# espnative-deadrail-2-7-rendered.net
KiCad netlist of a schematic drawn in EAGLE
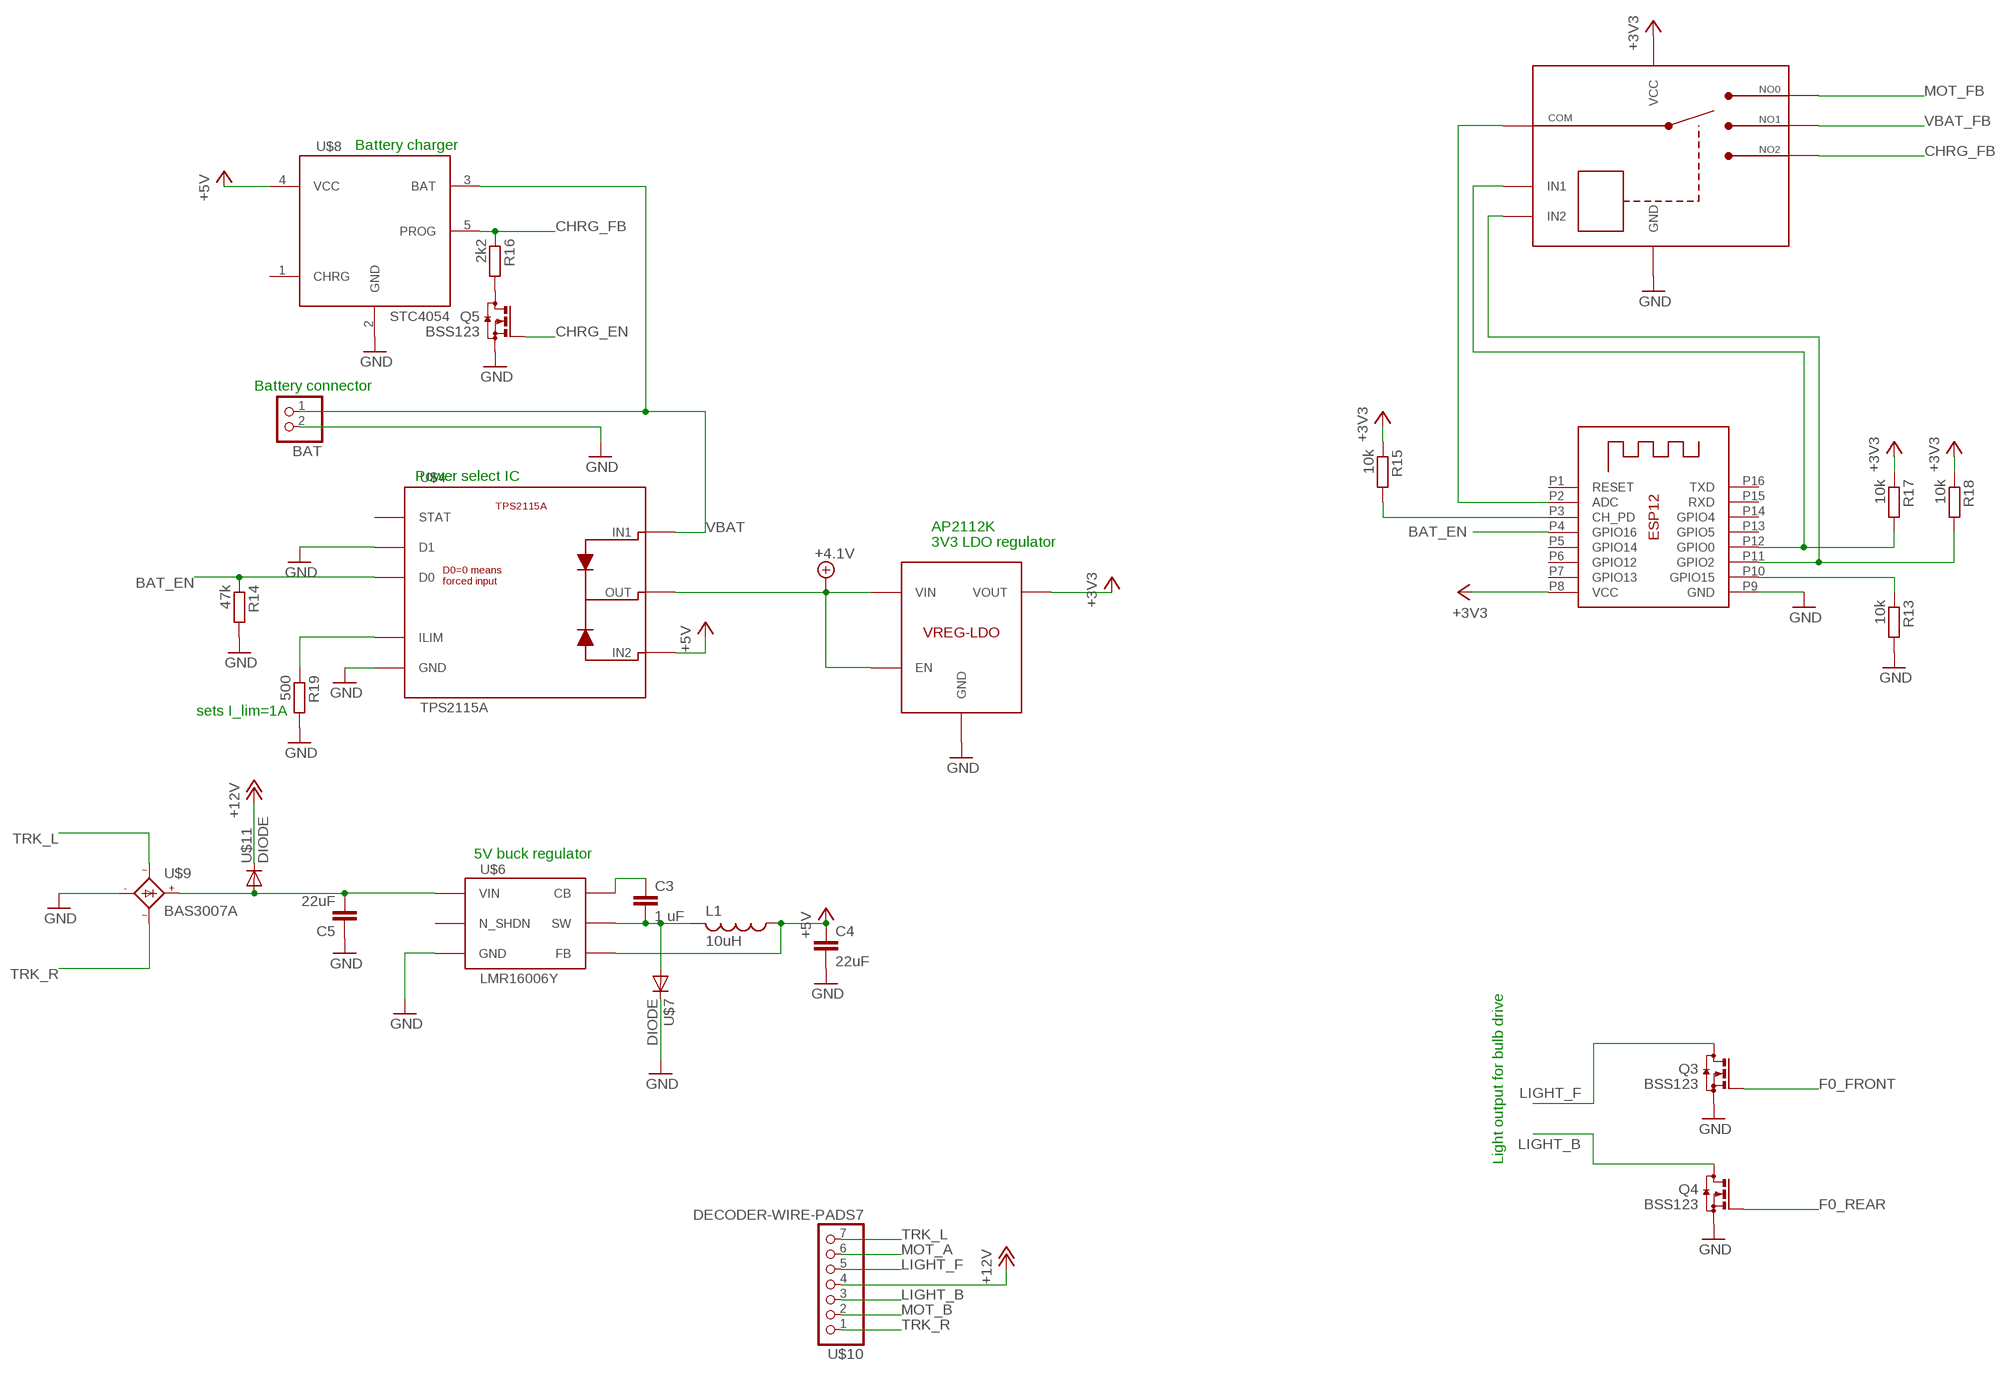
[diagram p0: schematic, sheet 1, part 1 of 2]
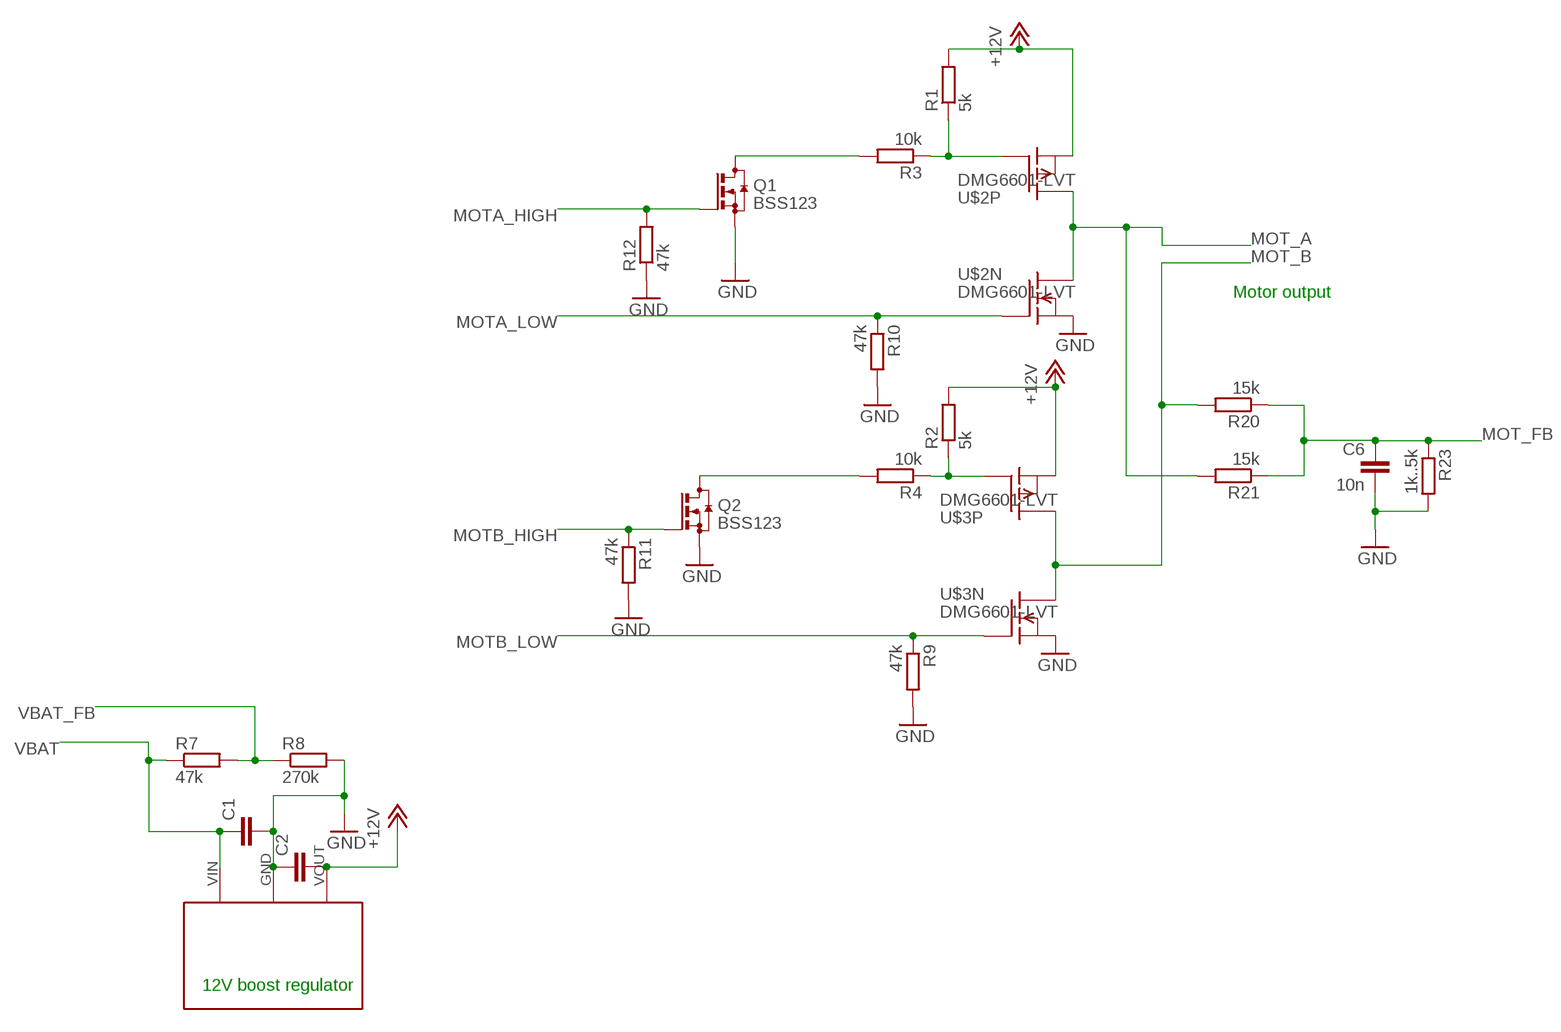
[diagram p1: schematic, sheet 1, part 2 of 2]

(export (version "E")
  (design (tool "Eeschema 10.0.6"))
  (components
    (comp (ref "BAT")
      (value "JST_2PIN-SMT-RA")
      (footprint "eagle-import:JST-PH-2-SMT-RA")
      (libsource (lib "eagle-import") (part "JST_2PIN-SMT-RA"))
    )
    (comp (ref "C1")
      (value "C-EUC1206")
      (footprint "eagle-import:C1206")
      (libsource (lib "eagle-import") (part "C-EUC1206"))
    )
    (comp (ref "C2")
      (value "C-EUC1206")
      (footprint "eagle-import:C1206")
      (libsource (lib "eagle-import") (part "C-EUC1206"))
    )
    (comp (ref "C3")
      (value "1 uF")
      (footprint "eagle-import:C0603")
      (libsource (lib "eagle-import") (part "C-EUC0603"))
    )
    (comp (ref "C4")
      (value "22uF")
      (footprint "eagle-import:C0603")
      (libsource (lib "eagle-import") (part "C-EUC0603"))
    )
    (comp (ref "C5")
      (value "22uF")
      (footprint "eagle-import:C1206")
      (libsource (lib "eagle-import") (part "C-EUC1206"))
    )
    (comp (ref "C6")
      (value "10n")
      (footprint "eagle-import:C0603")
      (libsource (lib "eagle-import") (part "C-EUC0603"))
    )
    (comp (ref "L1")
      (value "10uH")
      (footprint "eagle-import:FDSD0420")
      (libsource (lib "eagle-import") (part "FDSD0420"))
    )
    (comp (ref "Q1")
      (value "BSS123")
      (footprint "eagle-import:SOT23")
      (libsource (lib "eagle-import") (part "BSS123"))
    )
    (comp (ref "Q2")
      (value "BSS123")
      (footprint "eagle-import:SOT23")
      (libsource (lib "eagle-import") (part "BSS123"))
    )
    (comp (ref "Q3")
      (value "BSS123")
      (footprint "eagle-import:SOT23")
      (libsource (lib "eagle-import") (part "BSS123"))
    )
    (comp (ref "Q4")
      (value "BSS123")
      (footprint "eagle-import:SOT23")
      (libsource (lib "eagle-import") (part "BSS123"))
    )
    (comp (ref "Q5")
      (value "BSS123")
      (footprint "eagle-import:SOT23")
      (libsource (lib "eagle-import") (part "BSS123"))
    )
    (comp (ref "R1")
      (value "5k")
      (footprint "eagle-import:R0603")
      (libsource (lib "eagle-import") (part "R-EU_R0603"))
    )
    (comp (ref "R2")
      (value "5k")
      (footprint "eagle-import:R0603")
      (libsource (lib "eagle-import") (part "R-EU_R0603"))
    )
    (comp (ref "R3")
      (value "10k")
      (footprint "eagle-import:R0603")
      (libsource (lib "eagle-import") (part "R-EU_R0603"))
    )
    (comp (ref "R4")
      (value "10k")
      (footprint "eagle-import:R0603")
      (libsource (lib "eagle-import") (part "R-EU_R0603"))
    )
    (comp (ref "R7")
      (value "47k")
      (footprint "eagle-import:R0603")
      (libsource (lib "eagle-import") (part "R-EU_R0603"))
    )
    (comp (ref "R8")
      (value "270k")
      (footprint "eagle-import:R0603")
      (libsource (lib "eagle-import") (part "R-EU_R0603"))
    )
    (comp (ref "R9")
      (value "47k")
      (footprint "eagle-import:R0603")
      (libsource (lib "eagle-import") (part "R-EU_R0603"))
    )
    (comp (ref "R10")
      (value "47k")
      (footprint "eagle-import:R0603")
      (libsource (lib "eagle-import") (part "R-EU_R0603"))
    )
    (comp (ref "R11")
      (value "47k")
      (footprint "eagle-import:R0603")
      (libsource (lib "eagle-import") (part "R-EU_R0603"))
    )
    (comp (ref "R12")
      (value "47k")
      (footprint "eagle-import:R0603")
      (libsource (lib "eagle-import") (part "R-EU_R0603"))
    )
    (comp (ref "R13")
      (value "10k")
      (footprint "eagle-import:R0603")
      (libsource (lib "eagle-import") (part "R-EU_R0603"))
    )
    (comp (ref "R14")
      (value "47k")
      (footprint "eagle-import:R0603")
      (libsource (lib "eagle-import") (part "R-EU_R0603"))
    )
    (comp (ref "R15")
      (value "10k")
      (footprint "eagle-import:R0603")
      (libsource (lib "eagle-import") (part "R-EU_R0603"))
    )
    (comp (ref "R16")
      (value "2k2")
      (footprint "eagle-import:R0603")
      (libsource (lib "eagle-import") (part "R-EU_R0603"))
    )
    (comp (ref "R17")
      (value "10k")
      (footprint "eagle-import:R0603")
      (libsource (lib "eagle-import") (part "R-EU_R0603"))
    )
    (comp (ref "R18")
      (value "10k")
      (footprint "eagle-import:R0603")
      (libsource (lib "eagle-import") (part "R-EU_R0603"))
    )
    (comp (ref "R19")
      (value "500")
      (footprint "eagle-import:R0603")
      (libsource (lib "eagle-import") (part "R-EU_R0603"))
    )
    (comp (ref "R20")
      (value "15k")
      (footprint "eagle-import:R0603")
      (libsource (lib "eagle-import") (part "R-EU_R0603"))
    )
    (comp (ref "R21")
      (value "15k")
      (footprint "eagle-import:R0603")
      (libsource (lib "eagle-import") (part "R-EU_R0603"))
    )
    (comp (ref "R23")
      (value "1k..5k")
      (footprint "eagle-import:R0603")
      (libsource (lib "eagle-import") (part "R-EU_R0603"))
    )
    (comp (ref "U$1")
      (value "AP2112K-3V3")
      (footprint "eagle-import:SOT23-5L")
      (libsource (lib "eagle-import") (part "AP2112K"))
    )
    (comp (ref "U$2")
      (value "DMG6601-LVT")
      (footprint "eagle-import:TSOT-26")
      (libsource (lib "eagle-import") (part "DMG6601-LVT"))
    )
    (comp (ref "U$3")
      (value "DMG6601-LVT")
      (footprint "eagle-import:TSOT-26")
      (libsource (lib "eagle-import") (part "DMG6601-LVT"))
    )
    (comp (ref "U$4")
      (value "TPS2115A")
      (footprint "eagle-import:TSSOP-8")
      (libsource (lib "eagle-import") (part "TPS2115A"))
    )
    (comp (ref "U$5")
      (value "POLOLU-VREG12")
      (footprint "eagle-import:POLOLU-REGULATOR")
      (libsource (lib "eagle-import") (part "POLOLU-VREG12"))
    )
    (comp (ref "U$6")
      (value "LMR16006Y")
      (footprint "eagle-import:SOT23-6")
      (libsource (lib "eagle-import") (part "LMR16006Y"))
    )
    (comp (ref "U$7")
      (value "DIODE")
      (footprint "eagle-import:DIODE-1206")
      (libsource (lib "eagle-import") (part "DIODE"))
    )
    (comp (ref "U$8")
      (value "STC4054")
      (footprint "eagle-import:SOT23-5L")
      (libsource (lib "eagle-import") (part "STC4054"))
    )
    (comp (ref "U$9")
      (value "BAS3007A")
      (footprint "eagle-import:SOT143B")
      (libsource (lib "eagle-import") (part "BAS3007A"))
    )
    (comp (ref "U$10")
      (value "DECODER-WIRE-PADS7")
      (footprint "eagle-import:DECODER-WIRE-PADS")
      (libsource (lib "eagle-import") (part "DECODER-WIRE-PADS7"))
    )
    (comp (ref "U$11")
      (value "DIODE")
      (footprint "eagle-import:DIODE-1206")
      (libsource (lib "eagle-import") (part "DIODE"))
    )
    (comp (ref "U$12")
      (value "TS5A3359")
      (footprint "eagle-import:US8")
      (libsource (lib "eagle-import") (part "TS5A3359"))
    )
    (comp (ref "X1")
      (value "ESP-12-TH")
      (footprint "eagle-import:ESP-12-TH")
      (libsource (lib "eagle-import") (part "ESP-12-TH"))
    )
  )
  (nets
    (net (code "1") (name "+3V3") (class "Default")
      (node (ref "R15") (pin "1") (pinfunction "1_1") (pintype "passive"))
      (node (ref "R17") (pin "1") (pinfunction "1_1") (pintype "passive"))
      (node (ref "R18") (pin "1") (pinfunction "1_1") (pintype "passive"))
      (node (ref "U$1") (pin "5") (pinfunction "VOUT_5") (pintype "bidirectional"))
      (node (ref "U$12") (pin "8") (pinfunction "VCC_8") (pintype "bidirectional"))
      (node (ref "X1") (pin "P8") (pinfunction "VCC_P8") (pintype "power_in"))
    )
    (net (code "2") (name "+4.1V") (class "Default")
      (node (ref "U$1") (pin "1") (pinfunction "VIN_1") (pintype "bidirectional"))
      (node (ref "U$1") (pin "3") (pinfunction "EN_3") (pintype "bidirectional"))
      (node (ref "U$4") (pin "7") (pinfunction "OUT_7") (pintype "bidirectional"))
    )
    (net (code "3") (name "+5V") (class "Default")
      (node (ref "C4") (pin "1") (pinfunction "1_1") (pintype "passive"))
      (node (ref "L1") (pin "P$1") (pinfunction "1_P$1") (pintype "passive"))
      (node (ref "U$4") (pin "6") (pinfunction "IN2_6") (pintype "bidirectional"))
      (node (ref "U$6") (pin "3") (pinfunction "FB_3") (pintype "bidirectional"))
      (node (ref "U$8") (pin "4") (pinfunction "VCC_4") (pintype "bidirectional"))
    )
    (net (code "4") (name "+12V") (class "Default")
      (node (ref "C2") (pin "2") (pinfunction "2_2") (pintype "passive"))
      (node (ref "R1") (pin "2") (pinfunction "2_2") (pintype "passive"))
      (node (ref "R2") (pin "2") (pinfunction "2_2") (pintype "passive"))
      (node (ref "U$10") (pin "4") (pinfunction "4_4") (pintype "passive"))
      (node (ref "U$11") (pin "C") (pinfunction "C_C") (pintype "passive"))
      (node (ref "U$2") (pin "2") (pinfunction "S_2") (pintype "passive"))
      (node (ref "U$3") (pin "2") (pinfunction "S_2") (pintype "passive"))
      (node (ref "U$5") (pin "VOUT") (pinfunction "VOUT_VOUT") (pintype "bidirectional"))
    )
    (net (code "5") (name "/BAT_EN") (class "Default")
      (node (ref "R14") (pin "1") (pinfunction "1_1") (pintype "passive"))
      (node (ref "U$4") (pin "2") (pinfunction "D0_2") (pintype "bidirectional"))
      (node (ref "X1") (pin "P4") (pinfunction "GPIO16_P4") (pintype "bidirectional"))
    )
    (net (code "6") (name "/CHRG_EN") (class "Default")
      (node (ref "Q5") (pin "1") (pinfunction "G_1") (pintype "passive"))
    )
    (net (code "7") (name "/CHRG_FB") (class "Default")
      (node (ref "R16") (pin "1") (pinfunction "1_1") (pintype "passive"))
      (node (ref "U$12") (pin "3") (pinfunction "NO2_3") (pintype "bidirectional"))
      (node (ref "U$8") (pin "5") (pinfunction "PROG_5") (pintype "bidirectional"))
    )
    (net (code "8") (name "/F0_FRONT") (class "Default")
      (node (ref "Q3") (pin "1") (pinfunction "G_1") (pintype "passive"))
    )
    (net (code "9") (name "/F0_REAR") (class "Default")
      (node (ref "Q4") (pin "1") (pinfunction "G_1") (pintype "passive"))
    )
    (net (code "10") (name "/LIGHT_B") (class "Default")
      (node (ref "Q4") (pin "3") (pinfunction "D_3") (pintype "passive"))
      (node (ref "U$10") (pin "3") (pinfunction "3_3") (pintype "passive"))
    )
    (net (code "11") (name "/LIGHT_F") (class "Default")
      (node (ref "Q3") (pin "3") (pinfunction "D_3") (pintype "passive"))
      (node (ref "U$10") (pin "5") (pinfunction "5_5") (pintype "passive"))
    )
    (net (code "12") (name "/MOTA_HIGH") (class "Default")
      (node (ref "Q1") (pin "1") (pinfunction "G_1") (pintype "passive"))
      (node (ref "R12") (pin "2") (pinfunction "2_2") (pintype "passive"))
    )
    (net (code "13") (name "/MOTA_LOW") (class "Default")
      (node (ref "R10") (pin "1") (pinfunction "1_1") (pintype "passive"))
      (node (ref "U$2") (pin "1") (pinfunction "G_1") (pintype "passive"))
    )
    (net (code "14") (name "/MOTB_HIGH") (class "Default")
      (node (ref "Q2") (pin "1") (pinfunction "G_1") (pintype "passive"))
      (node (ref "R11") (pin "1") (pinfunction "1_1") (pintype "passive"))
    )
    (net (code "15") (name "/MOTB_LOW") (class "Default")
      (node (ref "R9") (pin "1") (pinfunction "1_1") (pintype "passive"))
      (node (ref "U$3") (pin "1") (pinfunction "G_1") (pintype "passive"))
    )
    (net (code "16") (name "/MOT_A") (class "Default")
      (node (ref "R21") (pin "2") (pinfunction "2_2") (pintype "passive"))
      (node (ref "U$10") (pin "6") (pinfunction "6_6") (pintype "passive"))
      (node (ref "U$2") (pin "4") (pinfunction "D_4") (pintype "passive"))
      (node (ref "U$2") (pin "6") (pinfunction "D_6") (pintype "passive"))
    )
    (net (code "17") (name "/MOT_B") (class "Default")
      (node (ref "R20") (pin "2") (pinfunction "2_2") (pintype "passive"))
      (node (ref "U$10") (pin "2") (pinfunction "2_2") (pintype "passive"))
      (node (ref "U$3") (pin "4") (pinfunction "D_4") (pintype "passive"))
      (node (ref "U$3") (pin "6") (pinfunction "D_6") (pintype "passive"))
    )
    (net (code "18") (name "/MOT_FB") (class "Default")
      (node (ref "C6") (pin "1") (pinfunction "1_1") (pintype "passive"))
      (node (ref "R20") (pin "1") (pinfunction "1_1") (pintype "passive"))
      (node (ref "R21") (pin "1") (pinfunction "1_1") (pintype "passive"))
      (node (ref "R23") (pin "1") (pinfunction "1_1") (pintype "passive"))
      (node (ref "U$12") (pin "1") (pinfunction "NO0_1") (pintype "bidirectional"))
    )
    (net (code "19") (name "/TRK_L") (class "Default")
      (node (ref "U$10") (pin "7") (pinfunction "7_7") (pintype "passive"))
      (node (ref "U$9") (pin "2") (pinfunction "AC1_2") (pintype "passive"))
    )
    (net (code "20") (name "/TRK_R") (class "Default")
      (node (ref "U$10") (pin "1") (pinfunction "1_1") (pintype "passive"))
      (node (ref "U$9") (pin "3") (pinfunction "AC2_3") (pintype "passive"))
    )
    (net (code "21") (name "/VBAT") (class "Default")
      (node (ref "BAT") (pin "1") (pinfunction "2_1") (pintype "passive"))
      (node (ref "C1") (pin "1") (pinfunction "1_1") (pintype "passive"))
      (node (ref "R7") (pin "1") (pinfunction "1_1") (pintype "passive"))
      (node (ref "U$4") (pin "8") (pinfunction "IN1_8") (pintype "bidirectional"))
      (node (ref "U$5") (pin "VIN") (pinfunction "VIN_VIN") (pintype "bidirectional"))
      (node (ref "U$8") (pin "3") (pinfunction "BAT_3") (pintype "bidirectional"))
    )
    (net (code "22") (name "/VBAT_FB") (class "Default")
      (node (ref "R7") (pin "2") (pinfunction "2_2") (pintype "passive"))
      (node (ref "R8") (pin "1") (pinfunction "1_1") (pintype "passive"))
      (node (ref "U$12") (pin "2") (pinfunction "NO1_2") (pintype "bidirectional"))
    )
    (net (code "23") (name "GND") (class "Default")
      (node (ref "BAT") (pin "2") (pinfunction "1_2") (pintype "passive"))
      (node (ref "C1") (pin "2") (pinfunction "2_2") (pintype "passive"))
      (node (ref "C2") (pin "1") (pinfunction "1_1") (pintype "passive"))
      (node (ref "C4") (pin "2") (pinfunction "2_2") (pintype "passive"))
      (node (ref "C5") (pin "1") (pinfunction "1_1") (pintype "passive"))
      (node (ref "C6") (pin "2") (pinfunction "2_2") (pintype "passive"))
      (node (ref "Q1") (pin "2") (pinfunction "S_2") (pintype "passive"))
      (node (ref "Q2") (pin "2") (pinfunction "S_2") (pintype "passive"))
      (node (ref "Q3") (pin "2") (pinfunction "S_2") (pintype "passive"))
      (node (ref "Q4") (pin "2") (pinfunction "S_2") (pintype "passive"))
      (node (ref "Q5") (pin "2") (pinfunction "S_2") (pintype "passive"))
      (node (ref "R10") (pin "2") (pinfunction "2_2") (pintype "passive"))
      (node (ref "R11") (pin "2") (pinfunction "2_2") (pintype "passive"))
      (node (ref "R12") (pin "1") (pinfunction "1_1") (pintype "passive"))
      (node (ref "R13") (pin "2") (pinfunction "2_2") (pintype "passive"))
      (node (ref "R14") (pin "2") (pinfunction "2_2") (pintype "passive"))
      (node (ref "R19") (pin "2") (pinfunction "2_2") (pintype "passive"))
      (node (ref "R23") (pin "2") (pinfunction "2_2") (pintype "passive"))
      (node (ref "R8") (pin "2") (pinfunction "2_2") (pintype "passive"))
      (node (ref "R9") (pin "2") (pinfunction "2_2") (pintype "passive"))
      (node (ref "U$1") (pin "2") (pinfunction "GND_2") (pintype "bidirectional"))
      (node (ref "U$12") (pin "4") (pinfunction "GND_4") (pintype "bidirectional"))
      (node (ref "U$2") (pin "5") (pinfunction "S_5") (pintype "passive"))
      (node (ref "U$3") (pin "5") (pinfunction "S_5") (pintype "passive"))
      (node (ref "U$4") (pin "3") (pinfunction "D1_3") (pintype "bidirectional"))
      (node (ref "U$4") (pin "5") (pinfunction "GND_5") (pintype "bidirectional"))
      (node (ref "U$5") (pin "GND") (pinfunction "GND_GND") (pintype "bidirectional"))
      (node (ref "U$6") (pin "2") (pinfunction "GND_2") (pintype "bidirectional"))
      (node (ref "U$7") (pin "C") (pinfunction "C_C") (pintype "passive"))
      (node (ref "U$8") (pin "2") (pinfunction "GND_2") (pintype "bidirectional"))
      (node (ref "U$9") (pin "1") (pinfunction "-_1") (pintype "passive"))
      (node (ref "X1") (pin "P9") (pinfunction "GND_P9") (pintype "power_in"))
    )
    (net (code "24") (name "Net-(L1-2)") (class "Default")
      (node (ref "C3") (pin "2") (pinfunction "2_2") (pintype "passive"))
      (node (ref "L1") (pin "P$2") (pinfunction "2_P$2") (pintype "passive"))
      (node (ref "U$6") (pin "6") (pinfunction "SW_6") (pintype "bidirectional"))
      (node (ref "U$7") (pin "A") (pinfunction "A_A") (pintype "passive"))
    )
    (net (code "25") (name "Net-(Q1-D)") (class "Default")
      (node (ref "Q1") (pin "3") (pinfunction "D_3") (pintype "passive"))
      (node (ref "R3") (pin "2") (pinfunction "2_2") (pintype "passive"))
    )
    (net (code "26") (name "Net-(Q2-D)") (class "Default")
      (node (ref "Q2") (pin "3") (pinfunction "D_3") (pintype "passive"))
      (node (ref "R4") (pin "2") (pinfunction "2_2") (pintype "passive"))
    )
    (net (code "27") (name "Net-(Q5-D)") (class "Default")
      (node (ref "Q5") (pin "3") (pinfunction "D_3") (pintype "passive"))
      (node (ref "R16") (pin "2") (pinfunction "2_2") (pintype "passive"))
    )
    (net (code "28") (name "Net-(U$2B-G)") (class "Default")
      (node (ref "R1") (pin "1") (pinfunction "1_1") (pintype "passive"))
      (node (ref "R3") (pin "1") (pinfunction "1_1") (pintype "passive"))
      (node (ref "U$2") (pin "3") (pinfunction "G_3") (pintype "passive"))
    )
    (net (code "29") (name "Net-(U$3B-G)") (class "Default")
      (node (ref "R2") (pin "1") (pinfunction "1_1") (pintype "passive"))
      (node (ref "R4") (pin "1") (pinfunction "1_1") (pintype "passive"))
      (node (ref "U$3") (pin "3") (pinfunction "G_3") (pintype "passive"))
    )
    (net (code "30") (name "Net-(U$4-ILIM)") (class "Default")
      (node (ref "R19") (pin "1") (pinfunction "1_1") (pintype "passive"))
      (node (ref "U$4") (pin "4") (pinfunction "ILIM_4") (pintype "bidirectional"))
    )
    (net (code "31") (name "Net-(U$6-CB)") (class "Default")
      (node (ref "C3") (pin "1") (pinfunction "1_1") (pintype "passive"))
      (node (ref "U$6") (pin "1") (pinfunction "CB_1") (pintype "bidirectional"))
    )
    (net (code "32") (name "Net-(U$6-VIN)") (class "Default")
      (node (ref "C5") (pin "2") (pinfunction "2_2") (pintype "passive"))
      (node (ref "U$11") (pin "A") (pinfunction "A_A") (pintype "passive"))
      (node (ref "U$6") (pin "5") (pinfunction "VIN_5") (pintype "bidirectional"))
      (node (ref "U$9") (pin "4") (pinfunction "+_4") (pintype "passive"))
    )
    (net (code "33") (name "Net-(U$12-COM)") (class "Default")
      (node (ref "U$12") (pin "7") (pinfunction "COM_7") (pintype "bidirectional"))
      (node (ref "X1") (pin "P2") (pinfunction "ADC_P2") (pintype "passive"))
    )
    (net (code "34") (name "Net-(U$12-IN1)") (class "Default")
      (node (ref "R17") (pin "2") (pinfunction "2_2") (pintype "passive"))
      (node (ref "U$12") (pin "6") (pinfunction "IN1_6") (pintype "bidirectional"))
      (node (ref "X1") (pin "P12") (pinfunction "GPIO0_P12") (pintype "bidirectional"))
    )
    (net (code "35") (name "Net-(U$12-IN2)") (class "Default")
      (node (ref "R18") (pin "2") (pinfunction "2_2") (pintype "passive"))
      (node (ref "U$12") (pin "5") (pinfunction "IN2_5") (pintype "bidirectional"))
      (node (ref "X1") (pin "P11") (pinfunction "GPIO2_P11") (pintype "bidirectional"))
    )
    (net (code "36") (name "Net-(X1-CH_PD)") (class "Default")
      (node (ref "R15") (pin "2") (pinfunction "2_2") (pintype "passive"))
      (node (ref "X1") (pin "P3") (pinfunction "CH_PD_P3") (pintype "input"))
    )
    (net (code "37") (name "Net-(X1-GPIO15)") (class "Default")
      (node (ref "R13") (pin "1") (pinfunction "1_1") (pintype "passive"))
      (node (ref "X1") (pin "P10") (pinfunction "GPIO15_P10") (pintype "bidirectional"))
    )
    (net (code "38") (name "unconnected-(U$4-STAT-Pad1)") (class "Default")
      (node (ref "U$4") (pin "1") (pinfunction "STAT_1") (pintype "bidirectional"))
    )
    (net (code "39") (name "unconnected-(U$6-N_SHDN-Pad4)") (class "Default")
      (node (ref "U$6") (pin "4") (pinfunction "N_SHDN_4") (pintype "bidirectional"))
    )
    (net (code "40") (name "unconnected-(U$8-CHRG-Pad1)") (class "Default")
      (node (ref "U$8") (pin "1") (pinfunction "CHRG_1") (pintype "bidirectional"))
    )
    (net (code "41") (name "unconnected-(X1-GPIO4-PadP14)") (class "Default")
      (node (ref "X1") (pin "P14") (pinfunction "GPIO4_P14") (pintype "bidirectional"))
    )
    (net (code "42") (name "unconnected-(X1-GPIO5-PadP13)") (class "Default")
      (node (ref "X1") (pin "P13") (pinfunction "GPIO5_P13") (pintype "bidirectional"))
    )
    (net (code "43") (name "unconnected-(X1-GPIO12-PadP6)") (class "Default")
      (node (ref "X1") (pin "P6") (pinfunction "GPIO12_P6") (pintype "bidirectional"))
    )
    (net (code "44") (name "unconnected-(X1-GPIO13-PadP7)") (class "Default")
      (node (ref "X1") (pin "P7") (pinfunction "GPIO13_P7") (pintype "bidirectional"))
    )
    (net (code "45") (name "unconnected-(X1-GPIO14-PadP5)") (class "Default")
      (node (ref "X1") (pin "P5") (pinfunction "GPIO14_P5") (pintype "bidirectional"))
    )
    (net (code "46") (name "unconnected-(X1-RESET-PadP1)") (class "Default")
      (node (ref "X1") (pin "P1") (pinfunction "RESET_P1") (pintype "input"))
    )
    (net (code "47") (name "unconnected-(X1-RXD-PadP15)") (class "Default")
      (node (ref "X1") (pin "P15") (pinfunction "RXD_P15") (pintype "input"))
    )
    (net (code "48") (name "unconnected-(X1-TXD-PadP16)") (class "Default")
      (node (ref "X1") (pin "P16") (pinfunction "TXD_P16") (pintype "output"))
    )
  )
)
